# Sheet1.net
KiCad netlist of a schematic drawn in Altium Designer
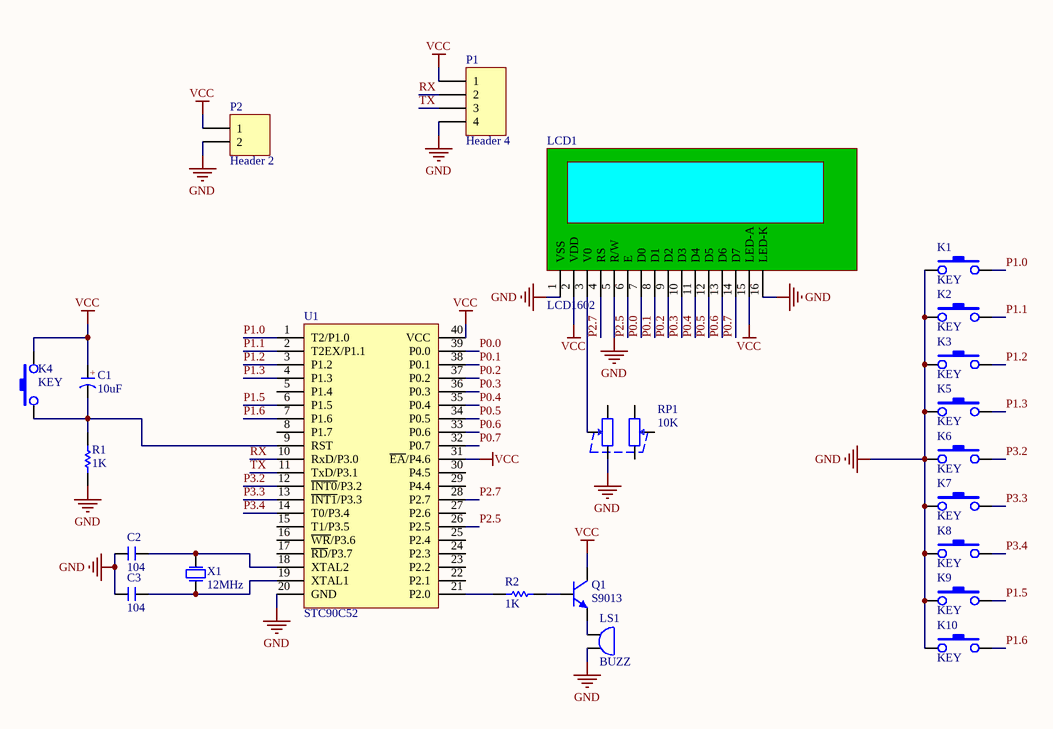
[diagram p0: Sheet1.SchDoc]

(export (version "E")
  (design (tool "Eeschema 10.0.6"))
  (components
    (comp (ref "C1")
      (value "10uF")
      (footprint "CAP 2.5*5*11")
      (description "直插电解电容")
      (libsource (lib "01 - 电容-电阻-电感") (part "CE"))
    )
    (comp (ref "C2")
      (value "104")
      (footprint "CC 1.8*3.6")
      (description "瓷片电容")
      (libsource (lib "01 - 电容-电阻-电感") (part "CC"))
    )
    (comp (ref "C3")
      (value "104")
      (footprint "CC 1.8*3.6")
      (description "瓷片电容")
      (libsource (lib "01 - 电容-电阻-电感") (part "CC"))
    )
    (comp (ref "K1")
      (value "KEY")
      (footprint "TSW DIP-6*6*5")
      (description "四角直插开关")
      (libsource (lib "03 - 按键-开关-晶振-蜂鸣器") (part "KEY"))
    )
    (comp (ref "K2")
      (value "KEY")
      (footprint "TSW DIP-6*6*5")
      (description "四角直插开关")
      (libsource (lib "03 - 按键-开关-晶振-蜂鸣器") (part "KEY"))
    )
    (comp (ref "K3")
      (value "KEY")
      (footprint "TSW DIP-6*6*5")
      (description "四角直插开关")
      (libsource (lib "03 - 按键-开关-晶振-蜂鸣器") (part "KEY"))
    )
    (comp (ref "K4")
      (value "KEY")
      (footprint "TSW DIP-6*6*5")
      (description "四角直插开关")
      (libsource (lib "03 - 按键-开关-晶振-蜂鸣器") (part "KEY"))
    )
    (comp (ref "K5")
      (value "KEY")
      (footprint "TSW DIP-6*6*5")
      (description "四角直插开关")
      (libsource (lib "03 - 按键-开关-晶振-蜂鸣器") (part "KEY"))
    )
    (comp (ref "K6")
      (value "KEY")
      (footprint "TSW DIP-6*6*5")
      (description "四角直插开关")
      (libsource (lib "03 - 按键-开关-晶振-蜂鸣器") (part "KEY"))
    )
    (comp (ref "K7")
      (value "KEY")
      (footprint "TSW DIP-6*6*5")
      (description "四角直插开关")
      (libsource (lib "03 - 按键-开关-晶振-蜂鸣器") (part "KEY"))
    )
    (comp (ref "K8")
      (value "KEY")
      (footprint "TSW DIP-6*6*5")
      (description "四角直插开关")
      (libsource (lib "03 - 按键-开关-晶振-蜂鸣器") (part "KEY"))
    )
    (comp (ref "K9")
      (value "KEY")
      (footprint "TSW DIP-6*6*5")
      (description "四角直插开关")
      (libsource (lib "03 - 按键-开关-晶振-蜂鸣器") (part "KEY"))
    )
    (comp (ref "K10")
      (value "KEY")
      (footprint "TSW DIP-6*6*5")
      (description "四角直插开关")
      (libsource (lib "03 - 按键-开关-晶振-蜂鸣器") (part "KEY"))
    )
    (comp (ref "LCD1")
      (value "LCD1602")
      (footprint "LCD-1602")
      (libsource (lib "05 - 点阵-液晶-数码管-TFT") (part "LCD1602"))
    )
    (comp (ref "LS1")
      (value "BUZZ")
      (footprint "BEEP 5x9x5.5")
      (description "蜂鸣器")
      (libsource (lib "03 - 按键-开关-晶振-蜂鸣器") (part "BUZZ"))
    )
    (comp (ref "P1")
      (value "Header 4")
      (footprint "HDR1X4")
      (description "Header, 4-Pin")
      (fields (field (name "PUBLISHER") "Altium Limited"))
      (libsource (lib "Miscellaneous Connectors") (part "Header 4"))
    )
    (comp (ref "P2")
      (value "Header 2")
      (footprint "HDR1X2")
      (description "Header, 2-Pin")
      (fields (field (name "PUBLISHER") "Altium Limited"))
      (libsource (lib "Miscellaneous Connectors") (part "Header 2"))
    )
    (comp (ref "Q1")
      (value "S9013")
      (footprint "TO92A")
      (description "低频放大-NPN型")
      (libsource (lib "02 - 二极管(LED)-三极管-整流桥") (part "9013-DIP"))
    )
    (comp (ref "R1")
      (value "1K")
      (footprint "RS 1/4W")
      (description "色环电阻")
      (libsource (lib "01 - 电容-电阻-电感") (part "Res"))
    )
    (comp (ref "R2")
      (value "1K")
      (footprint "RS 1/4W")
      (description "色环电阻")
      (libsource (lib "01 - 电容-电阻-电感") (part "Res"))
    )
    (comp (ref "RP1")
      (value "10K")
      (footprint "WH148-2-G15")
      (description "双联电位器")
      (libsource (lib "01 - 电容-电阻-电感") (part "RP-WH148"))
    )
    (comp (ref "U1")
      (value "STC90C52")
      (footprint "DIP40-600")
      (description "STC单片机")
      (libsource (lib "25 - STC系列单片机") (part "STC90C52"))
    )
    (comp (ref "X1")
      (value "12MHz")
      (footprint "OSC HC-49S")
      (description "2脚无源脚晶振")
      (libsource (lib "03 - 按键-开关-晶振-蜂鸣器") (part "XTAL-2P"))
    )
  )
  (nets
    (net (code "1") (name "/P0.0") (class "Default")
      (node (ref "LCD1") (pin "7") (pinfunction "D0_7") (pintype "passive"))
      (node (ref "U1") (pin "39") (pinfunction "P0.0_39") (pintype "passive"))
    )
    (net (code "2") (name "/P0.1") (class "Default")
      (node (ref "LCD1") (pin "8") (pinfunction "D1_8") (pintype "passive"))
      (node (ref "U1") (pin "38") (pinfunction "P0.1_38") (pintype "passive"))
    )
    (net (code "3") (name "/P0.2") (class "Default")
      (node (ref "LCD1") (pin "9") (pinfunction "D2_9") (pintype "passive"))
      (node (ref "U1") (pin "37") (pinfunction "P0.2_37") (pintype "passive"))
    )
    (net (code "4") (name "/P0.3") (class "Default")
      (node (ref "LCD1") (pin "10") (pinfunction "D3_10") (pintype "passive"))
      (node (ref "U1") (pin "36") (pinfunction "P0.3_36") (pintype "passive"))
    )
    (net (code "5") (name "/P0.4") (class "Default")
      (node (ref "LCD1") (pin "11") (pinfunction "D4_11") (pintype "passive"))
      (node (ref "U1") (pin "35") (pinfunction "P0.4_35") (pintype "passive"))
    )
    (net (code "6") (name "/P0.5") (class "Default")
      (node (ref "LCD1") (pin "12") (pinfunction "D5_12") (pintype "passive"))
      (node (ref "U1") (pin "34") (pinfunction "P0.5_34") (pintype "passive"))
    )
    (net (code "7") (name "/P0.6") (class "Default")
      (node (ref "LCD1") (pin "13") (pinfunction "D6_13") (pintype "passive"))
      (node (ref "U1") (pin "33") (pinfunction "P0.6_33") (pintype "passive"))
    )
    (net (code "8") (name "/P0.7") (class "Default")
      (node (ref "LCD1") (pin "14") (pinfunction "D7_14") (pintype "passive"))
      (node (ref "U1") (pin "32") (pinfunction "P0.7_32") (pintype "passive"))
    )
    (net (code "9") (name "/P1.0") (class "Default")
      (node (ref "K1") (pin "2") (pinfunction "2_2") (pintype "passive"))
      (node (ref "U1") (pin "1") (pinfunction "T2/P1.0_1") (pintype "passive"))
    )
    (net (code "10") (name "/P1.1") (class "Default")
      (node (ref "K2") (pin "2") (pinfunction "2_2") (pintype "passive"))
      (node (ref "U1") (pin "2") (pinfunction "T2EX/P1.1_2") (pintype "passive"))
    )
    (net (code "11") (name "/P1.2") (class "Default")
      (node (ref "K3") (pin "2") (pinfunction "2_2") (pintype "passive"))
      (node (ref "U1") (pin "3") (pinfunction "P1.2_3") (pintype "passive"))
    )
    (net (code "12") (name "/P1.3") (class "Default")
      (node (ref "K5") (pin "2") (pinfunction "2_2") (pintype "passive"))
      (node (ref "U1") (pin "4") (pinfunction "P1.3_4") (pintype "passive"))
    )
    (net (code "13") (name "/P1.5") (class "Default")
      (node (ref "K9") (pin "2") (pinfunction "2_2") (pintype "passive"))
      (node (ref "U1") (pin "6") (pinfunction "P1.5_6") (pintype "passive"))
    )
    (net (code "14") (name "/P1.6") (class "Default")
      (node (ref "K10") (pin "2") (pinfunction "2_2") (pintype "passive"))
      (node (ref "U1") (pin "7") (pinfunction "P1.6_7") (pintype "passive"))
    )
    (net (code "15") (name "/P2.5") (class "Default")
      (node (ref "LCD1") (pin "6") (pinfunction "E_6") (pintype "passive"))
      (node (ref "U1") (pin "26") (pinfunction "P2.5_26") (pintype "passive"))
    )
    (net (code "16") (name "/P2.7") (class "Default")
      (node (ref "LCD1") (pin "4") (pinfunction "RS_4") (pintype "passive"))
      (node (ref "U1") (pin "28") (pinfunction "P2.7_28") (pintype "passive"))
    )
    (net (code "17") (name "/P3.2") (class "Default")
      (node (ref "K6") (pin "2") (pinfunction "2_2") (pintype "passive"))
      (node (ref "U1") (pin "12") (pinfunction "~{INT0}/P3.2_12") (pintype "passive"))
    )
    (net (code "18") (name "/P3.3") (class "Default")
      (node (ref "K7") (pin "2") (pinfunction "2_2") (pintype "passive"))
      (node (ref "U1") (pin "13") (pinfunction "~{INT1}/P3.3_13") (pintype "passive"))
    )
    (net (code "19") (name "/P3.4") (class "Default")
      (node (ref "K8") (pin "2") (pinfunction "2_2") (pintype "passive"))
      (node (ref "U1") (pin "14") (pinfunction "T0/P3.4_14") (pintype "passive"))
    )
    (net (code "20") (name "/RX") (class "Default")
      (node (ref "P1") (pin "2") (pinfunction "2_2") (pintype "passive"))
      (node (ref "U1") (pin "10") (pinfunction "RxD/P3.0_10") (pintype "passive"))
    )
    (net (code "21") (name "/TX") (class "Default")
      (node (ref "P1") (pin "3") (pinfunction "3_3") (pintype "passive"))
      (node (ref "U1") (pin "11") (pinfunction "TxD/P3.1_11") (pintype "passive"))
    )
    (net (code "22") (name "GND") (class "Default")
      (node (ref "C2") (pin "1") (pinfunction "1_1") (pintype "passive"))
      (node (ref "C3") (pin "1") (pinfunction "1_1") (pintype "passive"))
      (node (ref "K1") (pin "1") (pinfunction "1_1") (pintype "passive"))
      (node (ref "K10") (pin "1") (pinfunction "1_1") (pintype "passive"))
      (node (ref "K2") (pin "1") (pinfunction "1_1") (pintype "passive"))
      (node (ref "K3") (pin "1") (pinfunction "1_1") (pintype "passive"))
      (node (ref "K5") (pin "1") (pinfunction "1_1") (pintype "passive"))
      (node (ref "K6") (pin "1") (pinfunction "1_1") (pintype "passive"))
      (node (ref "K7") (pin "1") (pinfunction "1_1") (pintype "passive"))
      (node (ref "K8") (pin "1") (pinfunction "1_1") (pintype "passive"))
      (node (ref "K9") (pin "1") (pinfunction "1_1") (pintype "passive"))
      (node (ref "LCD1") (pin "1") (pinfunction "VSS_1") (pintype "passive"))
      (node (ref "LCD1") (pin "16") (pinfunction "LED-K_16") (pintype "passive"))
      (node (ref "LCD1") (pin "5") (pinfunction "R/W_5") (pintype "passive"))
      (node (ref "LS1") (pin "2") (pinfunction "2_2") (pintype "passive"))
      (node (ref "P1") (pin "4") (pinfunction "4_4") (pintype "passive"))
      (node (ref "P2") (pin "2") (pinfunction "2_2") (pintype "passive"))
      (node (ref "R1") (pin "1") (pinfunction "1_1") (pintype "passive"))
      (node (ref "RP1") (pin "3") (pinfunction "3_3") (pintype "passive"))
      (node (ref "U1") (pin "20") (pinfunction "GND_20") (pintype "passive"))
    )
    (net (code "23") (name "Net-(C1-K)") (class "Default")
      (node (ref "C1") (pin "2") (pinfunction "K_2") (pintype "passive"))
      (node (ref "K4") (pin "1") (pinfunction "1_1") (pintype "passive"))
      (node (ref "R1") (pin "2") (pinfunction "2_2") (pintype "passive"))
      (node (ref "U1") (pin "9") (pinfunction "RST_9") (pintype "passive"))
    )
    (net (code "24") (name "Net-(LCD1-V0)") (class "Default")
      (node (ref "LCD1") (pin "3") (pinfunction "V0_3") (pintype "passive"))
      (node (ref "RP1") (pin "2") (pinfunction "2_2") (pintype "passive"))
    )
    (net (code "25") (name "Net-(Q1-B)") (class "Default")
      (node (ref "Q1") (pin "2") (pinfunction "B_2") (pintype "passive"))
      (node (ref "R2") (pin "1") (pinfunction "1_1") (pintype "passive"))
    )
    (net (code "26") (name "Net-(Q1-E)") (class "Default")
      (node (ref "LS1") (pin "1") (pinfunction "1_1") (pintype "passive"))
      (node (ref "Q1") (pin "1") (pinfunction "E_1") (pintype "passive"))
    )
    (net (code "27") (name "Net-(U1-P2.0)") (class "Default")
      (node (ref "R2") (pin "2") (pinfunction "2_2") (pintype "passive"))
      (node (ref "U1") (pin "21") (pinfunction "P2.0_21") (pintype "passive"))
    )
    (net (code "28") (name "Net-(U1-XTAL1)") (class "Default")
      (node (ref "C3") (pin "2") (pinfunction "2_2") (pintype "passive"))
      (node (ref "U1") (pin "19") (pinfunction "XTAL1_19") (pintype "passive"))
      (node (ref "X1") (pin "1") (pinfunction "1_1") (pintype "passive"))
    )
    (net (code "29") (name "Net-(U1-XTAL2)") (class "Default")
      (node (ref "C2") (pin "2") (pinfunction "2_2") (pintype "passive"))
      (node (ref "U1") (pin "18") (pinfunction "XTAL2_18") (pintype "passive"))
      (node (ref "X1") (pin "2") (pinfunction "2_2") (pintype "passive"))
    )
    (net (code "30") (name "VCC") (class "Default")
      (node (ref "C1") (pin "1") (pinfunction "A_1") (pintype "passive"))
      (node (ref "K4") (pin "2") (pinfunction "2_2") (pintype "passive"))
      (node (ref "LCD1") (pin "15") (pinfunction "LED-A_15") (pintype "passive"))
      (node (ref "LCD1") (pin "2") (pinfunction "VDD_2") (pintype "passive"))
      (node (ref "P1") (pin "1") (pinfunction "1_1") (pintype "passive"))
      (node (ref "P2") (pin "1") (pinfunction "1_1") (pintype "passive"))
      (node (ref "Q1") (pin "3") (pinfunction "C_3") (pintype "passive"))
      (node (ref "U1") (pin "31") (pinfunction "~{EA}/P4.6_31") (pintype "passive"))
      (node (ref "U1") (pin "40") (pinfunction "VCC_40") (pintype "passive"))
    )
    (net (code "31") (name "unconnected-(RP1-Pad1)") (class "Default")
      (node (ref "RP1") (pin "1") (pinfunction "1_1") (pintype "passive"))
    )
    (net (code "32") (name "unconnected-(RP1-Pad4)") (class "Default")
      (node (ref "RP1") (pin "4") (pinfunction "4_4") (pintype "passive"))
    )
    (net (code "33") (name "unconnected-(RP1-Pad5)") (class "Default")
      (node (ref "RP1") (pin "5") (pinfunction "5_5") (pintype "passive"))
    )
    (net (code "34") (name "unconnected-(RP1-Pad6)") (class "Default")
      (node (ref "RP1") (pin "6") (pinfunction "6_6") (pintype "passive"))
    )
    (net (code "35") (name "unconnected-(U1-P1.4-Pad5)") (class "Default")
      (node (ref "U1") (pin "5") (pinfunction "P1.4_5") (pintype "passive"))
    )
    (net (code "36") (name "unconnected-(U1-P1.7-Pad8)") (class "Default")
      (node (ref "U1") (pin "8") (pinfunction "P1.7_8") (pintype "passive"))
    )
    (net (code "37") (name "unconnected-(U1-P2.1-Pad22)") (class "Default")
      (node (ref "U1") (pin "22") (pinfunction "P2.1_22") (pintype "passive"))
    )
    (net (code "38") (name "unconnected-(U1-P2.2-Pad23)") (class "Default")
      (node (ref "U1") (pin "23") (pinfunction "P2.2_23") (pintype "passive"))
    )
    (net (code "39") (name "unconnected-(U1-P2.3-Pad24)") (class "Default")
      (node (ref "U1") (pin "24") (pinfunction "P2.3_24") (pintype "passive"))
    )
    (net (code "40") (name "unconnected-(U1-P2.4-Pad25)") (class "Default")
      (node (ref "U1") (pin "25") (pinfunction "P2.4_25") (pintype "passive"))
    )
    (net (code "41") (name "unconnected-(U1-P2.6-Pad27)") (class "Default")
      (node (ref "U1") (pin "27") (pinfunction "P2.6_27") (pintype "passive"))
    )
    (net (code "42") (name "unconnected-(U1-P4.4-Pad29)") (class "Default")
      (node (ref "U1") (pin "29") (pinfunction "P4.4_29") (pintype "passive"))
    )
    (net (code "43") (name "unconnected-(U1-P4.5-Pad30)") (class "Default")
      (node (ref "U1") (pin "30") (pinfunction "P4.5_30") (pintype "passive"))
    )
    (net (code "44") (name "unconnected-(U1-T1{slash}P3.5-Pad15)") (class "Default")
      (node (ref "U1") (pin "15") (pinfunction "T1/P3.5_15") (pintype "passive"))
    )
    (net (code "45") (name "unconnected-(U1-~{RD}{slash}P3.7-Pad17)") (class "Default")
      (node (ref "U1") (pin "17") (pinfunction "~{RD}/P3.7_17") (pintype "passive"))
    )
    (net (code "46") (name "unconnected-(U1-~{WR}{slash}P3.6-Pad16)") (class "Default")
      (node (ref "U1") (pin "16") (pinfunction "~{WR}/P3.6_16") (pintype "passive"))
    )
  )
)
